# corex2.net
KiCad netlist of a schematic drawn in EAGLE
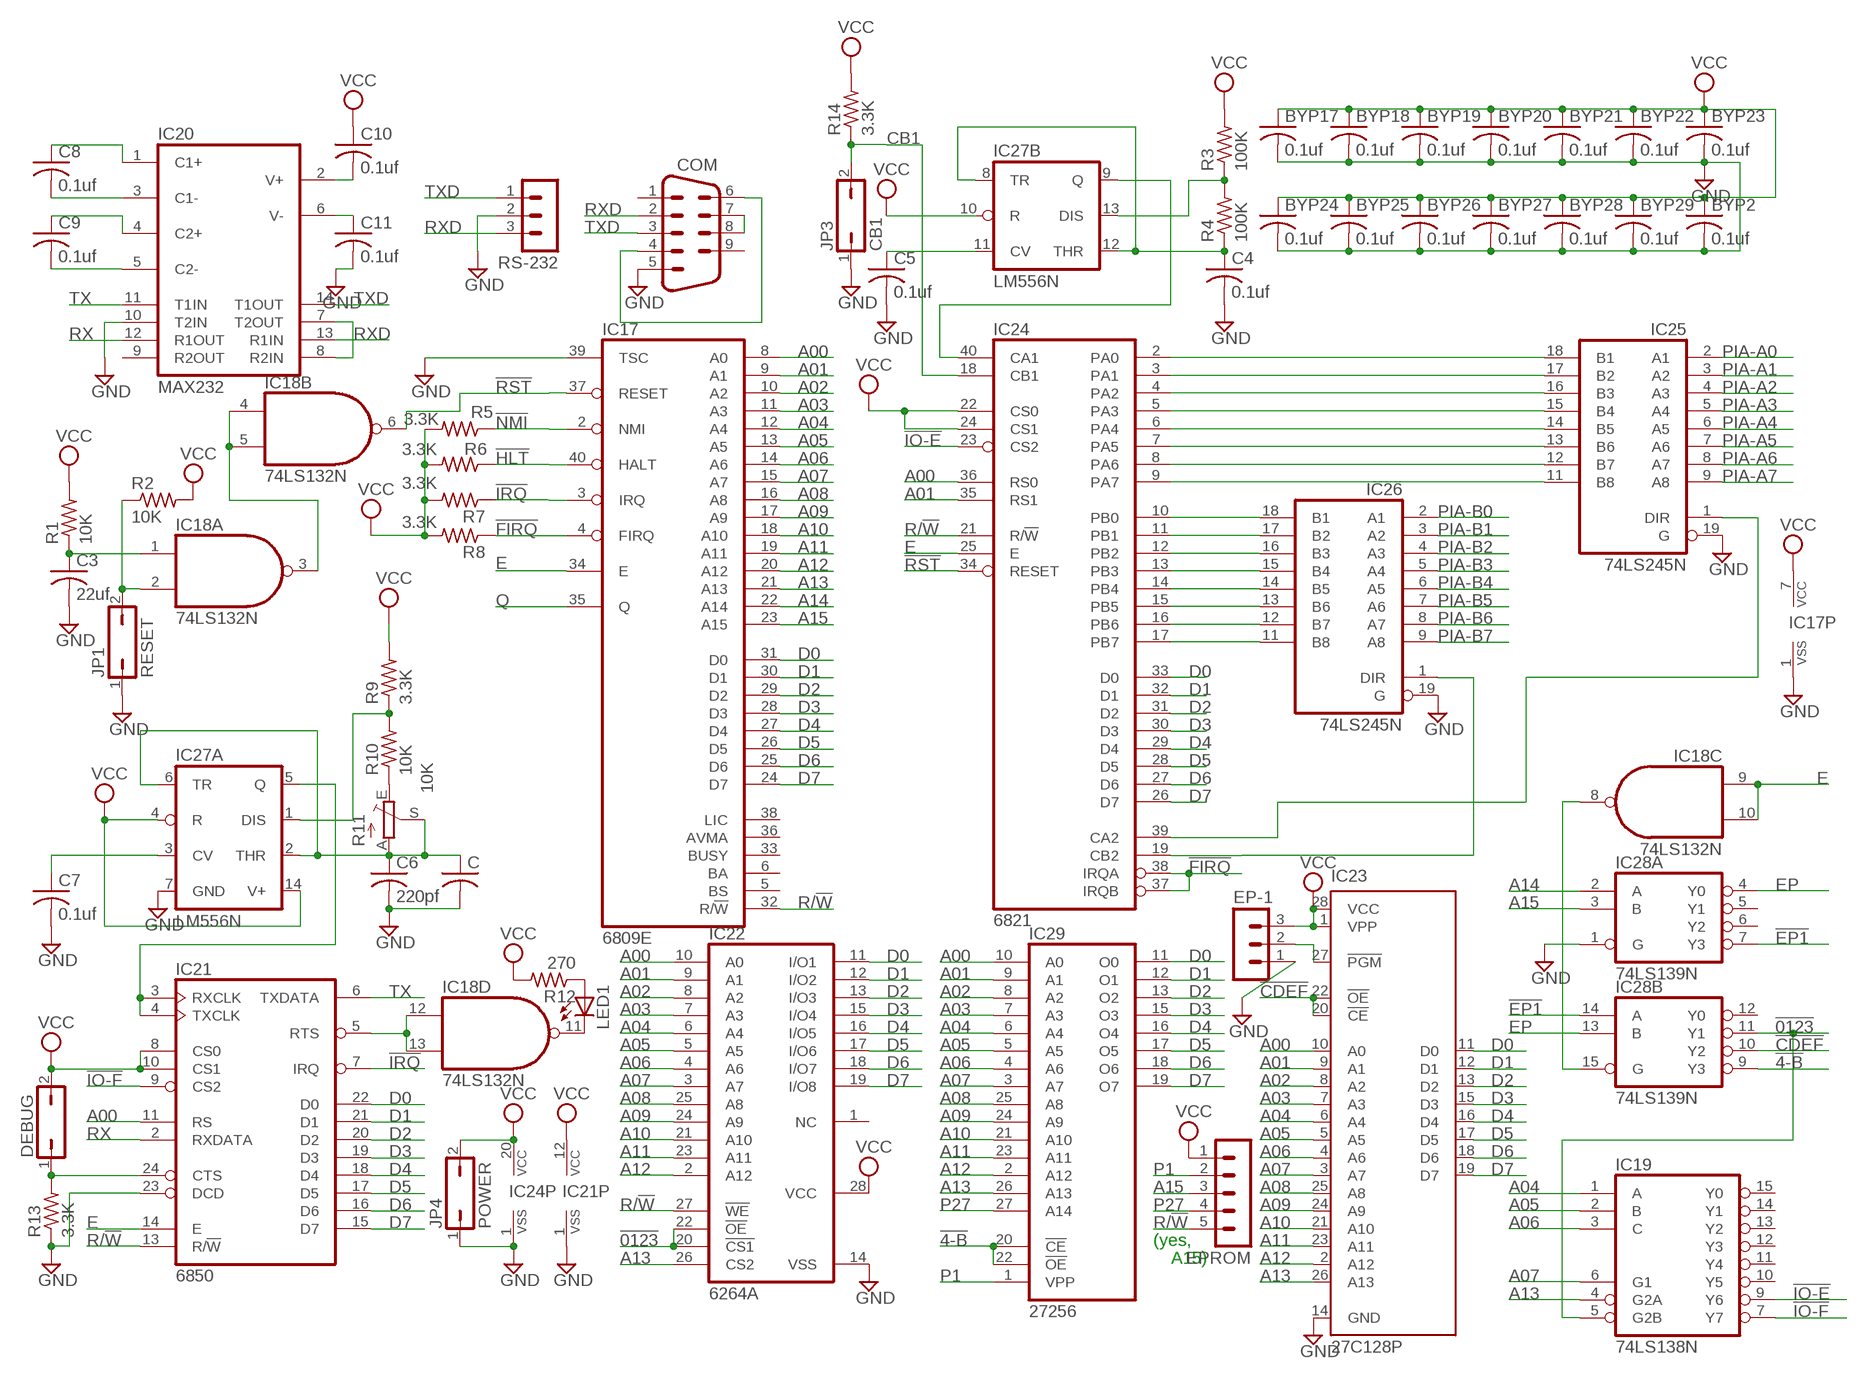
[diagram p0: schematic, sheet 1]
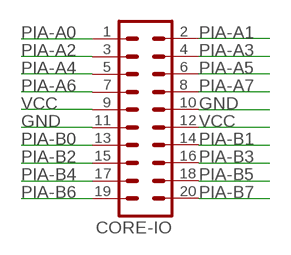
[diagram p1: schematic, sheet 2]
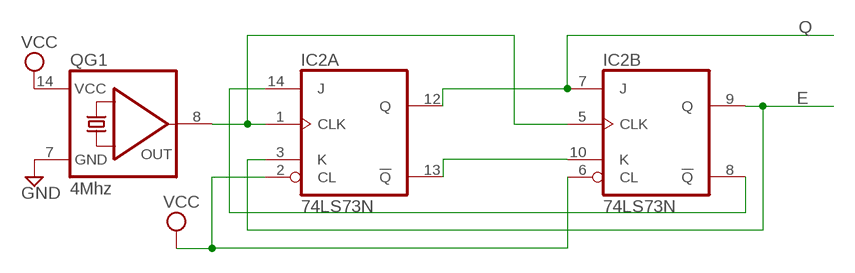
[diagram p2: schematic, sheet 3]

(export (version "E")
  (design (tool "Eeschema 10.0.6"))
  (components
    (comp (ref "CORE-IO")
      (value "MA10-2")
      (footprint "eagle-import:MA10-2")
      (libsource (lib "eagle-import") (part "MA10-2"))
    )
    (comp (ref "BYP2")
      (value "0.1uf")
      (footprint "eagle-import:C050-025X075")
      (libsource (lib "eagle-import") (part "C-US050-025X075"))
    )
    (comp (ref "BYP17")
      (value "0.1uf")
      (footprint "eagle-import:C050-025X075")
      (libsource (lib "eagle-import") (part "C-US050-025X075"))
    )
    (comp (ref "BYP18")
      (value "0.1uf")
      (footprint "eagle-import:C050-025X075")
      (libsource (lib "eagle-import") (part "C-US050-025X075"))
    )
    (comp (ref "BYP19")
      (value "0.1uf")
      (footprint "eagle-import:C050-025X075")
      (libsource (lib "eagle-import") (part "C-US050-025X075"))
    )
    (comp (ref "BYP20")
      (value "0.1uf")
      (footprint "eagle-import:C050-025X075")
      (libsource (lib "eagle-import") (part "C-US050-025X075"))
    )
    (comp (ref "BYP21")
      (value "0.1uf")
      (footprint "eagle-import:C050-025X075")
      (libsource (lib "eagle-import") (part "C-US050-025X075"))
    )
    (comp (ref "BYP22")
      (value "0.1uf")
      (footprint "eagle-import:C050-025X075")
      (libsource (lib "eagle-import") (part "C-US050-025X075"))
    )
    (comp (ref "BYP23")
      (value "0.1uf")
      (footprint "eagle-import:C050-025X075")
      (libsource (lib "eagle-import") (part "C-US050-025X075"))
    )
    (comp (ref "BYP24")
      (value "0.1uf")
      (footprint "eagle-import:C050-025X075")
      (libsource (lib "eagle-import") (part "C-US050-025X075"))
    )
    (comp (ref "BYP25")
      (value "0.1uf")
      (footprint "eagle-import:C050-025X075")
      (libsource (lib "eagle-import") (part "C-US050-025X075"))
    )
    (comp (ref "BYP26")
      (value "0.1uf")
      (footprint "eagle-import:C050-025X075")
      (libsource (lib "eagle-import") (part "C-US050-025X075"))
    )
    (comp (ref "BYP27")
      (value "0.1uf")
      (footprint "eagle-import:C050-025X075")
      (libsource (lib "eagle-import") (part "C-US050-025X075"))
    )
    (comp (ref "BYP28")
      (value "0.1uf")
      (footprint "eagle-import:C050-025X075")
      (libsource (lib "eagle-import") (part "C-US050-025X075"))
    )
    (comp (ref "BYP29")
      (value "0.1uf")
      (footprint "eagle-import:C050-025X075")
      (libsource (lib "eagle-import") (part "C-US050-025X075"))
    )
    (comp (ref "C")
      (value "C-US050-025X075")
      (footprint "eagle-import:C050-025X075")
      (libsource (lib "eagle-import") (part "C-US050-025X075"))
    )
    (comp (ref "C3")
      (value "22uf")
      (footprint "eagle-import:C102-054X133")
      (libsource (lib "eagle-import") (part "C-US102-054X133"))
    )
    (comp (ref "C4")
      (value "0.1uf")
      (footprint "eagle-import:C050-025X075")
      (libsource (lib "eagle-import") (part "C-US050-025X075"))
    )
    (comp (ref "C5")
      (value "0.1uf")
      (footprint "eagle-import:C050-025X075")
      (libsource (lib "eagle-import") (part "C-US050-025X075"))
    )
    (comp (ref "C6")
      (value "220pf")
      (footprint "eagle-import:C050-025X075")
      (libsource (lib "eagle-import") (part "C-US050-025X075"))
    )
    (comp (ref "C7")
      (value "0.1uf")
      (footprint "eagle-import:C050-025X075")
      (libsource (lib "eagle-import") (part "C-US050-025X075"))
    )
    (comp (ref "C8")
      (value "0.1uf")
      (footprint "eagle-import:C050-025X075")
      (libsource (lib "eagle-import") (part "C-US050-025X075"))
    )
    (comp (ref "C9")
      (value "0.1uf")
      (footprint "eagle-import:C050-025X075")
      (libsource (lib "eagle-import") (part "C-US050-025X075"))
    )
    (comp (ref "C10")
      (value "0.1uf")
      (footprint "eagle-import:C050-025X075")
      (libsource (lib "eagle-import") (part "C-US050-025X075"))
    )
    (comp (ref "C11")
      (value "0.1uf")
      (footprint "eagle-import:C050-025X075")
      (libsource (lib "eagle-import") (part "C-US050-025X075"))
    )
    (comp (ref "COM")
      (value "M09HP")
      (footprint "eagle-import:M09HP")
      (libsource (lib "eagle-import") (part "M09HP"))
    )
    (comp (ref "DEBUG")
      (value "JP1Q")
      (footprint "eagle-import:JP1")
      (libsource (lib "eagle-import") (part "JP1Q"))
    )
    (comp (ref "EP-1")
      (value "MA03-1")
      (footprint "eagle-import:MA03-1")
      (libsource (lib "eagle-import") (part "MA03-1"))
    )
    (comp (ref "EPROM")
      (value "MA05-1")
      (footprint "eagle-import:MA05-1")
      (libsource (lib "eagle-import") (part "MA05-1"))
    )
    (comp (ref "IC17")
      (value "6809E")
      (footprint "eagle-import:DIL40")
      (fields (field (name "MF") "NTE ELECTRONICS") (field (name "MPN") "NTE6809E"))
      (libsource (lib "eagle-import") (part "6809E"))
    )
    (comp (ref "IC18")
      (value "74LS132N")
      (footprint "eagle-import:DIL14")
      (libsource (lib "eagle-import") (part "7400NLS"))
    )
    (comp (ref "IC19")
      (value "74LS138N")
      (footprint "eagle-import:DIL16")
      (libsource (lib "eagle-import") (part "74138NLS"))
    )
    (comp (ref "IC20")
      (value "MAX232")
      (footprint "eagle-import:DIL16")
      (fields (field (name "MF") "MAXIM") (field (name "MPN") "MAX232ACPE+"))
      (libsource (lib "eagle-import") (part "MAX232"))
    )
    (comp (ref "IC21")
      (value "6850")
      (footprint "eagle-import:DIL24")
      (fields (field (name "MF") "NTE ELECTRONICS") (field (name "MPN") "NTE6850"))
      (libsource (lib "eagle-import") (part "6850"))
    )
    (comp (ref "IC22")
      (value "6264A")
      (footprint "eagle-import:DIL28-6")
      (libsource (lib "eagle-import") (part "6264A"))
    )
    (comp (ref "IC23")
      (value "27C128P")
      (footprint "eagle-import:DIL28-6")
      (libsource (lib "eagle-import") (part "27128PC"))
    )
    (comp (ref "IC24")
      (value "6821")
      (footprint "eagle-import:DIL40")
      (fields (field (name "MF") "NTE ELECTRONICS") (field (name "MPN") "NTE6821"))
      (libsource (lib "eagle-import") (part "6821"))
    )
    (comp (ref "IC25")
      (value "74LS245N")
      (footprint "eagle-import:DIL20")
      (libsource (lib "eagle-import") (part "74245NLS"))
    )
    (comp (ref "IC26")
      (value "74LS245N")
      (footprint "eagle-import:DIL20")
      (libsource (lib "eagle-import") (part "74245NLS"))
    )
    (comp (ref "IC27")
      (value "LM556N")
      (footprint "eagle-import:DIL14")
      (libsource (lib "eagle-import") (part "556NLM"))
    )
    (comp (ref "IC28")
      (value "74LS139N")
      (footprint "eagle-import:DIL16")
      (libsource (lib "eagle-import") (part "74139NLS"))
    )
    (comp (ref "IC29")
      (value "27256")
      (footprint "eagle-import:DIL28")
      (libsource (lib "eagle-import") (part "27256"))
    )
    (comp (ref "JP1")
      (value "RESET")
      (footprint "eagle-import:JP1")
      (libsource (lib "eagle-import") (part "JP1Q"))
    )
    (comp (ref "JP3")
      (value "CB1")
      (footprint "eagle-import:JP1")
      (libsource (lib "eagle-import") (part "JP1Q"))
    )
    (comp (ref "JP4")
      (value "POWER")
      (footprint "eagle-import:JP1")
      (libsource (lib "eagle-import") (part "JP1Q"))
    )
    (comp (ref "LED1")
      (value "LED3MM")
      (footprint "eagle-import:LED3MM")
      (libsource (lib "eagle-import") (part "LED3MM"))
    )
    (comp (ref "R1")
      (value "10K")
      (footprint "eagle-import:0207_7")
      (libsource (lib "eagle-import") (part "R-US_0207/7"))
    )
    (comp (ref "R2")
      (value "10K")
      (footprint "eagle-import:0207_7")
      (libsource (lib "eagle-import") (part "R-US_0207/7"))
    )
    (comp (ref "R3")
      (value "100K")
      (footprint "eagle-import:0207_7")
      (libsource (lib "eagle-import") (part "R-US_0207/7"))
    )
    (comp (ref "R4")
      (value "100K")
      (footprint "eagle-import:0207_7")
      (libsource (lib "eagle-import") (part "R-US_0207/7"))
    )
    (comp (ref "R5")
      (value "3.3K")
      (footprint "eagle-import:0207_7")
      (libsource (lib "eagle-import") (part "R-US_0207/7"))
    )
    (comp (ref "R6")
      (value "3.3K")
      (footprint "eagle-import:0207_7")
      (libsource (lib "eagle-import") (part "R-US_0207/7"))
    )
    (comp (ref "R7")
      (value "3.3K")
      (footprint "eagle-import:0207_7")
      (libsource (lib "eagle-import") (part "R-US_0207/7"))
    )
    (comp (ref "R8")
      (value "3.3K")
      (footprint "eagle-import:0207_7")
      (libsource (lib "eagle-import") (part "R-US_0207/7"))
    )
    (comp (ref "R9")
      (value "3.3K")
      (footprint "eagle-import:0207_7")
      (libsource (lib "eagle-import") (part "R-US_0207/7"))
    )
    (comp (ref "R10")
      (value "10K")
      (footprint "eagle-import:0207_7")
      (libsource (lib "eagle-import") (part "R-US_0207/7"))
    )
    (comp (ref "R11")
      (value "10K")
      (footprint "eagle-import:SP19L")
      (libsource (lib "eagle-import") (part "TRIM_EU-B90P"))
    )
    (comp (ref "R12")
      (value "270")
      (footprint "eagle-import:0207_7")
      (libsource (lib "eagle-import") (part "R-US_0207/7"))
    )
    (comp (ref "R13")
      (value "3.3K")
      (footprint "eagle-import:0207_7")
      (libsource (lib "eagle-import") (part "R-US_0207/7"))
    )
    (comp (ref "R14")
      (value "3.3K")
      (footprint "eagle-import:0207_7")
      (libsource (lib "eagle-import") (part "R-US_0207/7"))
    )
    (comp (ref "RS-232")
      (value "MA03-1")
      (footprint "eagle-import:MA03-1")
      (libsource (lib "eagle-import") (part "MA03-1"))
    )
    (comp (ref "IC2")
      (value "74LS73N")
      (footprint "eagle-import:DIL14")
      (libsource (lib "eagle-import") (part "7473NLS"))
    )
    (comp (ref "QG1")
      (value "4Mhz")
      (footprint "eagle-import:DIL14S")
      (libsource (lib "eagle-import") (part "QG5860"))
    )
  )
  (nets
    (net (code "1") (name "A00") (class "Default")
      (node (ref "IC17") (pin "8") (pinfunction "A0_8") (pintype "tri_state"))
      (node (ref "IC21") (pin "11") (pinfunction "RS_11") (pintype "input"))
      (node (ref "IC22") (pin "10") (pinfunction "A0_10") (pintype "input"))
      (node (ref "IC23") (pin "10") (pinfunction "A0_10") (pintype "input"))
      (node (ref "IC24") (pin "36") (pinfunction "RS0_36") (pintype "input"))
      (node (ref "IC29") (pin "10") (pinfunction "A0_10") (pintype "input"))
    )
    (net (code "2") (name "A01") (class "Default")
      (node (ref "IC17") (pin "9") (pinfunction "A1_9") (pintype "tri_state"))
      (node (ref "IC22") (pin "9") (pinfunction "A1_9") (pintype "input"))
      (node (ref "IC23") (pin "9") (pinfunction "A1_9") (pintype "input"))
      (node (ref "IC24") (pin "35") (pinfunction "RS1_35") (pintype "input"))
      (node (ref "IC29") (pin "9") (pinfunction "A1_9") (pintype "input"))
    )
    (net (code "3") (name "A02") (class "Default")
      (node (ref "IC17") (pin "10") (pinfunction "A2_10") (pintype "tri_state"))
      (node (ref "IC22") (pin "8") (pinfunction "A2_8") (pintype "input"))
      (node (ref "IC23") (pin "8") (pinfunction "A2_8") (pintype "input"))
      (node (ref "IC29") (pin "8") (pinfunction "A2_8") (pintype "input"))
    )
    (net (code "4") (name "A03") (class "Default")
      (node (ref "IC17") (pin "11") (pinfunction "A3_11") (pintype "tri_state"))
      (node (ref "IC22") (pin "7") (pinfunction "A3_7") (pintype "input"))
      (node (ref "IC23") (pin "7") (pinfunction "A3_7") (pintype "input"))
      (node (ref "IC29") (pin "7") (pinfunction "A3_7") (pintype "input"))
    )
    (net (code "5") (name "A04") (class "Default")
      (node (ref "IC17") (pin "12") (pinfunction "A4_12") (pintype "tri_state"))
      (node (ref "IC19") (pin "1") (pinfunction "A_1") (pintype "input"))
      (node (ref "IC22") (pin "6") (pinfunction "A4_6") (pintype "input"))
      (node (ref "IC23") (pin "6") (pinfunction "A4_6") (pintype "input"))
      (node (ref "IC29") (pin "6") (pinfunction "A4_6") (pintype "input"))
    )
    (net (code "6") (name "A05") (class "Default")
      (node (ref "IC17") (pin "13") (pinfunction "A5_13") (pintype "tri_state"))
      (node (ref "IC19") (pin "2") (pinfunction "B_2") (pintype "input"))
      (node (ref "IC22") (pin "5") (pinfunction "A5_5") (pintype "input"))
      (node (ref "IC23") (pin "5") (pinfunction "A5_5") (pintype "input"))
      (node (ref "IC29") (pin "5") (pinfunction "A5_5") (pintype "input"))
    )
    (net (code "7") (name "A06") (class "Default")
      (node (ref "IC17") (pin "14") (pinfunction "A6_14") (pintype "tri_state"))
      (node (ref "IC19") (pin "3") (pinfunction "C_3") (pintype "input"))
      (node (ref "IC22") (pin "4") (pinfunction "A6_4") (pintype "input"))
      (node (ref "IC23") (pin "4") (pinfunction "A6_4") (pintype "input"))
      (node (ref "IC29") (pin "4") (pinfunction "A6_4") (pintype "input"))
    )
    (net (code "8") (name "A07") (class "Default")
      (node (ref "IC17") (pin "15") (pinfunction "A7_15") (pintype "tri_state"))
      (node (ref "IC19") (pin "6") (pinfunction "G1_6") (pintype "input"))
      (node (ref "IC22") (pin "3") (pinfunction "A7_3") (pintype "input"))
      (node (ref "IC23") (pin "3") (pinfunction "A7_3") (pintype "input"))
      (node (ref "IC29") (pin "3") (pinfunction "A7_3") (pintype "input"))
    )
    (net (code "9") (name "A08") (class "Default")
      (node (ref "IC17") (pin "16") (pinfunction "A8_16") (pintype "tri_state"))
      (node (ref "IC22") (pin "25") (pinfunction "A8_25") (pintype "input"))
      (node (ref "IC23") (pin "25") (pinfunction "A8_25") (pintype "input"))
      (node (ref "IC29") (pin "25") (pinfunction "A8_25") (pintype "input"))
    )
    (net (code "10") (name "A09") (class "Default")
      (node (ref "IC17") (pin "17") (pinfunction "A9_17") (pintype "tri_state"))
      (node (ref "IC22") (pin "24") (pinfunction "A9_24") (pintype "input"))
      (node (ref "IC23") (pin "24") (pinfunction "A9_24") (pintype "input"))
      (node (ref "IC29") (pin "24") (pinfunction "A9_24") (pintype "input"))
    )
    (net (code "11") (name "A10") (class "Default")
      (node (ref "IC17") (pin "18") (pinfunction "A10_18") (pintype "tri_state"))
      (node (ref "IC22") (pin "21") (pinfunction "A10_21") (pintype "input"))
      (node (ref "IC23") (pin "21") (pinfunction "A10_21") (pintype "input"))
      (node (ref "IC29") (pin "21") (pinfunction "A10_21") (pintype "input"))
    )
    (net (code "12") (name "A11") (class "Default")
      (node (ref "IC17") (pin "19") (pinfunction "A11_19") (pintype "tri_state"))
      (node (ref "IC22") (pin "23") (pinfunction "A11_23") (pintype "input"))
      (node (ref "IC23") (pin "23") (pinfunction "A11_23") (pintype "input"))
      (node (ref "IC29") (pin "23") (pinfunction "A11_23") (pintype "input"))
    )
    (net (code "13") (name "A12") (class "Default")
      (node (ref "IC17") (pin "20") (pinfunction "A12_20") (pintype "tri_state"))
      (node (ref "IC22") (pin "2") (pinfunction "A12_2") (pintype "input"))
      (node (ref "IC23") (pin "2") (pinfunction "A12_2") (pintype "input"))
      (node (ref "IC29") (pin "2") (pinfunction "A12_2") (pintype "input"))
    )
    (net (code "14") (name "A13") (class "Default")
      (node (ref "IC17") (pin "21") (pinfunction "A13_21") (pintype "tri_state"))
      (node (ref "IC19") (pin "4") (pinfunction "G2A_4") (pintype "input"))
      (node (ref "IC22") (pin "26") (pinfunction "CS2_26") (pintype "input"))
      (node (ref "IC23") (pin "26") (pinfunction "A13_26") (pintype "input"))
      (node (ref "IC29") (pin "26") (pinfunction "A13_26") (pintype "input"))
    )
    (net (code "15") (name "A14") (class "Default")
      (node (ref "IC17") (pin "22") (pinfunction "A14_22") (pintype "tri_state"))
      (node (ref "IC28") (pin "2") (pinfunction "A_2") (pintype "input"))
    )
    (net (code "16") (name "A15") (class "Default")
      (node (ref "EPROM") (pin "3") (pinfunction "3_3") (pintype "passive"))
      (node (ref "IC17") (pin "23") (pinfunction "A15_23") (pintype "tri_state"))
      (node (ref "IC28") (pin "3") (pinfunction "B_3") (pintype "input"))
    )
    (net (code "17") (name "CB1") (class "Default")
      (node (ref "IC24") (pin "18") (pinfunction "CB1_18") (pintype "input"))
      (node (ref "JP3") (pin "2") (pinfunction "2_2") (pintype "passive"))
      (node (ref "R14") (pin "1") (pinfunction "1_1") (pintype "passive"))
    )
    (net (code "18") (name "D0") (class "Default")
      (node (ref "IC17") (pin "31") (pinfunction "D0_31") (pintype "bidirectional"))
      (node (ref "IC21") (pin "22") (pinfunction "D0_22") (pintype "bidirectional"))
      (node (ref "IC22") (pin "11") (pinfunction "I/O1_11") (pintype "bidirectional"))
      (node (ref "IC23") (pin "11") (pinfunction "D0_11") (pintype "tri_state"))
      (node (ref "IC24") (pin "33") (pinfunction "D0_33") (pintype "bidirectional"))
      (node (ref "IC29") (pin "11") (pinfunction "O0_11") (pintype "tri_state"))
    )
    (net (code "19") (name "D1") (class "Default")
      (node (ref "IC17") (pin "30") (pinfunction "D1_30") (pintype "bidirectional"))
      (node (ref "IC21") (pin "21") (pinfunction "D1_21") (pintype "bidirectional"))
      (node (ref "IC22") (pin "12") (pinfunction "I/O2_12") (pintype "bidirectional"))
      (node (ref "IC23") (pin "12") (pinfunction "D1_12") (pintype "tri_state"))
      (node (ref "IC24") (pin "32") (pinfunction "D1_32") (pintype "bidirectional"))
      (node (ref "IC29") (pin "12") (pinfunction "O1_12") (pintype "tri_state"))
    )
    (net (code "20") (name "D2") (class "Default")
      (node (ref "IC17") (pin "29") (pinfunction "D2_29") (pintype "bidirectional"))
      (node (ref "IC21") (pin "20") (pinfunction "D2_20") (pintype "bidirectional"))
      (node (ref "IC22") (pin "13") (pinfunction "I/O3_13") (pintype "bidirectional"))
      (node (ref "IC23") (pin "13") (pinfunction "D2_13") (pintype "tri_state"))
      (node (ref "IC24") (pin "31") (pinfunction "D2_31") (pintype "bidirectional"))
      (node (ref "IC29") (pin "13") (pinfunction "O2_13") (pintype "tri_state"))
    )
    (net (code "21") (name "D3") (class "Default")
      (node (ref "IC17") (pin "28") (pinfunction "D3_28") (pintype "bidirectional"))
      (node (ref "IC21") (pin "19") (pinfunction "D3_19") (pintype "bidirectional"))
      (node (ref "IC22") (pin "15") (pinfunction "I/O4_15") (pintype "bidirectional"))
      (node (ref "IC23") (pin "15") (pinfunction "D3_15") (pintype "tri_state"))
      (node (ref "IC24") (pin "30") (pinfunction "D3_30") (pintype "bidirectional"))
      (node (ref "IC29") (pin "15") (pinfunction "O3_15") (pintype "tri_state"))
    )
    (net (code "22") (name "D4") (class "Default")
      (node (ref "IC17") (pin "27") (pinfunction "D4_27") (pintype "bidirectional"))
      (node (ref "IC21") (pin "18") (pinfunction "D4_18") (pintype "bidirectional"))
      (node (ref "IC22") (pin "16") (pinfunction "I/O5_16") (pintype "bidirectional"))
      (node (ref "IC23") (pin "16") (pinfunction "D4_16") (pintype "tri_state"))
      (node (ref "IC24") (pin "29") (pinfunction "D4_29") (pintype "bidirectional"))
      (node (ref "IC29") (pin "16") (pinfunction "O4_16") (pintype "tri_state"))
    )
    (net (code "23") (name "D5") (class "Default")
      (node (ref "IC17") (pin "26") (pinfunction "D5_26") (pintype "bidirectional"))
      (node (ref "IC21") (pin "17") (pinfunction "D5_17") (pintype "bidirectional"))
      (node (ref "IC22") (pin "17") (pinfunction "I/O6_17") (pintype "bidirectional"))
      (node (ref "IC23") (pin "17") (pinfunction "D5_17") (pintype "tri_state"))
      (node (ref "IC24") (pin "28") (pinfunction "D5_28") (pintype "bidirectional"))
      (node (ref "IC29") (pin "17") (pinfunction "O5_17") (pintype "tri_state"))
    )
    (net (code "24") (name "D6") (class "Default")
      (node (ref "IC17") (pin "25") (pinfunction "D6_25") (pintype "bidirectional"))
      (node (ref "IC21") (pin "16") (pinfunction "D6_16") (pintype "bidirectional"))
      (node (ref "IC22") (pin "18") (pinfunction "I/O7_18") (pintype "bidirectional"))
      (node (ref "IC23") (pin "18") (pinfunction "D6_18") (pintype "tri_state"))
      (node (ref "IC24") (pin "27") (pinfunction "D6_27") (pintype "bidirectional"))
      (node (ref "IC29") (pin "18") (pinfunction "O6_18") (pintype "tri_state"))
    )
    (net (code "25") (name "D7") (class "Default")
      (node (ref "IC17") (pin "24") (pinfunction "D7_24") (pintype "bidirectional"))
      (node (ref "IC21") (pin "15") (pinfunction "D7_15") (pintype "bidirectional"))
      (node (ref "IC22") (pin "19") (pinfunction "I/O8_19") (pintype "bidirectional"))
      (node (ref "IC23") (pin "19") (pinfunction "D7_19") (pintype "tri_state"))
      (node (ref "IC24") (pin "26") (pinfunction "D7_26") (pintype "bidirectional"))
      (node (ref "IC29") (pin "19") (pinfunction "O7_19") (pintype "tri_state"))
    )
    (net (code "26") (name "E") (class "Default")
      (node (ref "IC17") (pin "34") (pinfunction "E_34") (pintype "input"))
      (node (ref "IC18") (pin "10") (pinfunction "I1_10") (pintype "input"))
      (node (ref "IC18") (pin "9") (pinfunction "I0_9") (pintype "input"))
      (node (ref "IC2") (pin "3") (pinfunction "K_3") (pintype "input"))
      (node (ref "IC2") (pin "9") (pinfunction "Q_9") (pintype "output"))
      (node (ref "IC21") (pin "14") (pinfunction "E_14") (pintype "input"))
      (node (ref "IC24") (pin "25") (pinfunction "E_25") (pintype "input"))
    )
    (net (code "27") (name "EP") (class "Default")
      (node (ref "IC28") (pin "13") (pinfunction "B_13") (pintype "input"))
      (node (ref "IC28") (pin "4") (pinfunction "Y0_4") (pintype "output"))
    )
    (net (code "28") (name "GND") (class "Default")
      (node (ref "BYP17") (pin "2") (pinfunction "2_2") (pintype "passive"))
      (node (ref "BYP18") (pin "2") (pinfunction "2_2") (pintype "passive"))
      (node (ref "BYP19") (pin "2") (pinfunction "2_2") (pintype "passive"))
      (node (ref "BYP2") (pin "2") (pinfunction "2_2") (pintype "passive"))
      (node (ref "BYP20") (pin "2") (pinfunction "2_2") (pintype "passive"))
      (node (ref "BYP21") (pin "2") (pinfunction "2_2") (pintype "passive"))
      (node (ref "BYP22") (pin "2") (pinfunction "2_2") (pintype "passive"))
      (node (ref "BYP23") (pin "2") (pinfunction "2_2") (pintype "passive"))
      (node (ref "BYP24") (pin "2") (pinfunction "2_2") (pintype "passive"))
      (node (ref "BYP25") (pin "2") (pinfunction "2_2") (pintype "passive"))
      (node (ref "BYP26") (pin "2") (pinfunction "2_2") (pintype "passive"))
      (node (ref "BYP27") (pin "2") (pinfunction "2_2") (pintype "passive"))
      (node (ref "BYP28") (pin "2") (pinfunction "2_2") (pintype "passive"))
      (node (ref "BYP29") (pin "2") (pinfunction "2_2") (pintype "passive"))
      (node (ref "C") (pin "2") (pinfunction "2_2") (pintype "passive"))
      (node (ref "C11") (pin "2") (pinfunction "2_2") (pintype "passive"))
      (node (ref "C3") (pin "2") (pinfunction "2_2") (pintype "passive"))
      (node (ref "C4") (pin "2") (pinfunction "2_2") (pintype "passive"))
      (node (ref "C5") (pin "2") (pinfunction "2_2") (pintype "passive"))
      (node (ref "C6") (pin "2") (pinfunction "2_2") (pintype "passive"))
      (node (ref "C7") (pin "2") (pinfunction "2_2") (pintype "passive"))
      (node (ref "COM") (pin "5") (pinfunction "5_5") (pintype "passive"))
      (node (ref "CORE-IO") (pin "10") (pinfunction "10_10") (pintype "passive"))
      (node (ref "CORE-IO") (pin "11") (pinfunction "11_11") (pintype "passive"))
      (node (ref "EP-1") (pin "1") (pinfunction "1_1") (pintype "passive"))
      (node (ref "IC17") (pin "1") (pinfunction "VSS_1") (pintype "power_in"))
      (node (ref "IC17") (pin "39") (pinfunction "TSC_39") (pintype "input"))
      (node (ref "IC20") (pin "10") (pinfunction "T2IN_10") (pintype "input"))
      (node (ref "IC21") (pin "1") (pinfunction "VSS_1") (pintype "power_in"))
      (node (ref "IC21") (pin "23") (pinfunction "DCD_23") (pintype "input"))
      (node (ref "IC22") (pin "14") (pinfunction "VSS_14") (pintype "power_in"))
      (node (ref "IC23") (pin "14") (pinfunction "GND_14") (pintype "power_in"))
      (node (ref "IC24") (pin "1") (pinfunction "VSS_1") (pintype "power_in"))
      (node (ref "IC25") (pin "19") (pinfunction "G_19") (pintype "input"))
      (node (ref "IC26") (pin "19") (pinfunction "G_19") (pintype "input"))
      (node (ref "IC27") (pin "7") (pinfunction "GND_7") (pintype "power_in"))
      (node (ref "IC28") (pin "1") (pinfunction "G_1") (pintype "input"))
      (node (ref "JP1") (pin "1") (pinfunction "1_1") (pintype "passive"))
      (node (ref "JP3") (pin "1") (pinfunction "1_1") (pintype "passive"))
      (node (ref "JP4") (pin "1") (pinfunction "1_1") (pintype "passive"))
      (node (ref "QG1") (pin "7") (pinfunction "GND_7") (pintype "power_in"))
      (node (ref "R13") (pin "1") (pinfunction "1_1") (pintype "passive"))
      (node (ref "RS-232") (pin "2") (pinfunction "2_2") (pintype "passive"))
    )
    (net (code "29") (name "Net-(COM-Pad4)") (class "Default")
      (node (ref "COM") (pin "4") (pinfunction "4_4") (pintype "passive"))
      (node (ref "COM") (pin "6") (pinfunction "6_6") (pintype "passive"))
    )
    (net (code "30") (name "Net-(COM-Pad7)") (class "Default")
      (node (ref "COM") (pin "7") (pinfunction "7_7") (pintype "passive"))
      (node (ref "COM") (pin "8") (pinfunction "8_8") (pintype "passive"))
    )
    (net (code "31") (name "Net-(IC2A-CLK)") (class "Default")
      (node (ref "IC2") (pin "1") (pinfunction "CLK_1") (pintype "input"))
      (node (ref "IC2") (pin "5") (pinfunction "CLK_5") (pintype "input"))
      (node (ref "QG1") (pin "8") (pinfunction "OUT_8") (pintype "output"))
    )
    (net (code "32") (name "Net-(IC2A-J)") (class "Default")
      (node (ref "IC2") (pin "14") (pinfunction "J_14") (pintype "input"))
      (node (ref "IC2") (pin "8") (pinfunction "~{Q}_8") (pintype "output"))
    )
    (net (code "33") (name "Net-(IC2A-~{Q})") (class "Default")
      (node (ref "IC2") (pin "10") (pinfunction "K_10") (pintype "input"))
      (node (ref "IC2") (pin "13") (pinfunction "~{Q}_13") (pintype "output"))
    )
    (net (code "34") (name "Net-(IC18A-I0)") (class "Default")
      (node (ref "C3") (pin "1") (pinfunction "1_1") (pintype "passive"))
      (node (ref "IC18") (pin "1") (pinfunction "I0_1") (pintype "input"))
      (node (ref "R1") (pin "1") (pinfunction "1_1") (pintype "passive"))
    )
    (net (code "35") (name "Net-(IC18A-I1)") (class "Default")
      (node (ref "IC18") (pin "2") (pinfunction "I1_2") (pintype "input"))
      (node (ref "JP1") (pin "2") (pinfunction "2_2") (pintype "passive"))
      (node (ref "R2") (pin "1") (pinfunction "1_1") (pintype "passive"))
    )
    (net (code "36") (name "Net-(IC18A-O)") (class "Default")
      (node (ref "IC18") (pin "3") (pinfunction "O_3") (pintype "output"))
      (node (ref "IC18") (pin "4") (pinfunction "I0_4") (pintype "input"))
      (node (ref "IC18") (pin "5") (pinfunction "I1_5") (pintype "input"))
    )
    (net (code "37") (name "Net-(IC18C-O)") (class "Default")
      (node (ref "IC18") (pin "8") (pinfunction "O_8") (pintype "output"))
      (node (ref "IC28") (pin "15") (pinfunction "G_15") (pintype "input"))
    )
    (net (code "38") (name "Net-(IC18D-I0)") (class "Default")
      (node (ref "IC18") (pin "12") (pinfunction "I0_12") (pintype "input"))
      (node (ref "IC18") (pin "13") (pinfunction "I1_13") (pintype "input"))
      (node (ref "IC21") (pin "5") (pinfunction "RTS_5") (pintype "output"))
    )
    (net (code "39") (name "Net-(IC18D-O)") (class "Default")
      (node (ref "IC18") (pin "11") (pinfunction "O_11") (pintype "output"))
      (node (ref "LED1") (pin "K") (pinfunction "C_K") (pintype "passive"))
    )
    (net (code "40") (name "Net-(IC20A-C1+)") (class "Default")
      (node (ref "C8") (pin "1") (pinfunction "1_1") (pintype "passive"))
      (node (ref "IC20") (pin "1") (pinfunction "C1+_1") (pintype "bidirectional"))
    )
    (net (code "41") (name "Net-(IC20A-C1-)") (class "Default")
      (node (ref "C8") (pin "2") (pinfunction "2_2") (pintype "passive"))
      (node (ref "IC20") (pin "3") (pinfunction "C1-_3") (pintype "bidirectional"))
    )
    (net (code "42") (name "Net-(IC20A-C2+)") (class "Default")
      (node (ref "C9") (pin "1") (pinfunction "1_1") (pintype "passive"))
      (node (ref "IC20") (pin "4") (pinfunction "C2+_4") (pintype "bidirectional"))
    )
    (net (code "43") (name "Net-(IC20A-C2-)") (class "Default")
      (node (ref "C9") (pin "2") (pinfunction "2_2") (pintype "passive"))
      (node (ref "IC20") (pin "5") (pinfunction "C2-_5") (pintype "bidirectional"))
    )
    (net (code "44") (name "Net-(IC20A-R2IN)") (class "Default")
      (node (ref "IC20") (pin "7") (pinfunction "T2OUT_7") (pintype "output"))
      (node (ref "IC20") (pin "8") (pinfunction "R2IN_8") (pintype "input"))
    )
    (net (code "45") (name "Net-(IC20A-V+)") (class "Default")
      (node (ref "C10") (pin "2") (pinfunction "2_2") (pintype "passive"))
      (node (ref "IC20") (pin "2") (pinfunction "V+_2") (pintype "bidirectional"))
    )
    (net (code "46") (name "Net-(IC20A-V-)") (class "Default")
      (node (ref "C11") (pin "1") (pinfunction "1_1") (pintype "passive"))
      (node (ref "IC20") (pin "6") (pinfunction "V-_6") (pintype "bidirectional"))
    )
    (net (code "47") (name "Net-(IC21A-CTS)") (class "Default")
      (node (ref "DEBUG") (pin "1") (pinfunction "1_1") (pintype "passive"))
      (node (ref "IC21") (pin "24") (pinfunction "CTS_24") (pintype "input"))
      (node (ref "R13") (pin "2") (pinfunction "2_2") (pintype "passive"))
    )
    (net (code "48") (name "Net-(IC21A-RXCLK)") (class "Default")
      (node (ref "IC21") (pin "3") (pinfunction "RXCLK_3") (pintype "input"))
      (node (ref "IC21") (pin "4") (pinfunction "TXCLK_4") (pintype "input"))
      (node (ref "IC27") (pin "5") (pinfunction "Q_5") (pintype "output"))
    )
    (net (code "49") (name "Net-(IC23-~{PGM})") (class "Default")
      (node (ref "EP-1") (pin "2") (pinfunction "2_2") (pintype "passive"))
      (node (ref "IC23") (pin "27") (pinfunction "~{PGM}_27") (pintype "passive"))
    )
    (net (code "50") (name "Net-(IC24A-CA1)") (class "Default")
      (node (ref "IC24") (pin "40") (pinfunction "CA1_40") (pintype "input"))
      (node (ref "IC27") (pin "9") (pinfunction "Q_9") (pintype "output"))
    )
    (net (code "51") (name "Net-(IC24A-CA2)") (class "Default")
      (node (ref "IC24") (pin "39") (pinfunction "CA2_39") (pintype "bidirectional"))
      (node (ref "IC25") (pin "1") (pinfunction "DIR_1") (pintype "input"))
    )
    (net (code "52") (name "Net-(IC24A-CB2)") (class "Default")
      (node (ref "IC24") (pin "19") (pinfunction "CB2_19") (pintype "bidirectional"))
      (node (ref "IC26") (pin "1") (pinfunction "DIR_1") (pintype "input"))
    )
    (net (code "53") (name "Net-(IC24A-PA0)") (class "Default")
      (node (ref "IC24") (pin "2") (pinfunction "PA0_2") (pintype "bidirectional"))
      (node (ref "IC25") (pin "18") (pinfunction "B1_18") (pintype "bidirectional"))
    )
    (net (code "54") (name "Net-(IC24A-PA1)") (class "Default")
      (node (ref "IC24") (pin "3") (pinfunction "PA1_3") (pintype "bidirectional"))
      (node (ref "IC25") (pin "17") (pinfunction "B2_17") (pintype "bidirectional"))
    )
    (net (code "55") (name "Net-(IC24A-PA2)") (class "Default")
      (node (ref "IC24") (pin "4") (pinfunction "PA2_4") (pintype "bidirectional"))
      (node (ref "IC25") (pin "16") (pinfunction "B3_16") (pintype "bidirectional"))
    )
    (net (code "56") (name "Net-(IC24A-PA3)") (class "Default")
      (node (ref "IC24") (pin "5") (pinfunction "PA3_5") (pintype "bidirectional"))
      (node (ref "IC25") (pin "15") (pinfunction "B4_15") (pintype "bidirectional"))
    )
    (net (code "57") (name "Net-(IC24A-PA4)") (class "Default")
      (node (ref "IC24") (pin "6") (pinfunction "PA4_6") (pintype "bidirectional"))
      (node (ref "IC25") (pin "14") (pinfunction "B5_14") (pintype "bidirectional"))
    )
    (net (code "58") (name "Net-(IC24A-PA5)") (class "Default")
      (node (ref "IC24") (pin "7") (pinfunction "PA5_7") (pintype "bidirectional"))
      (node (ref "IC25") (pin "13") (pinfunction "B6_13") (pintype "bidirectional"))
    )
    (net (code "59") (name "Net-(IC24A-PA6)") (class "Default")
      (node (ref "IC24") (pin "8") (pinfunction "PA6_8") (pintype "bidirectional"))
      (node (ref "IC25") (pin "12") (pinfunction "B7_12") (pintype "bidirectional"))
    )
    (net (code "60") (name "Net-(IC24A-PA7)") (class "Default")
      (node (ref "IC24") (pin "9") (pinfunction "PA7_9") (pintype "bidirectional"))
      (node (ref "IC25") (pin "11") (pinfunction "B8_11") (pintype "bidirectional"))
    )
    (net (code "61") (name "Net-(IC24A-PB0)") (class "Default")
      (node (ref "IC24") (pin "10") (pinfunction "PB0_10") (pintype "bidirectional"))
      (node (ref "IC26") (pin "18") (pinfunction "B1_18") (pintype "bidirectional"))
    )
    (net (code "62") (name "Net-(IC24A-PB1)") (class "Default")
      (node (ref "IC24") (pin "11") (pinfunction "PB1_11") (pintype "bidirectional"))
      (node (ref "IC26") (pin "17") (pinfunction "B2_17") (pintype "bidirectional"))
    )
    (net (code "63") (name "Net-(IC24A-PB2)") (class "Default")
      (node (ref "IC24") (pin "12") (pinfunction "PB2_12") (pintype "bidirectional"))
      (node (ref "IC26") (pin "16") (pinfunction "B3_16") (pintype "bidirectional"))
    )
    (net (code "64") (name "Net-(IC24A-PB3)") (class "Default")
      (node (ref "IC24") (pin "13") (pinfunction "PB3_13") (pintype "bidirectional"))
      (node (ref "IC26") (pin "15") (pinfunction "B4_15") (pintype "bidirectional"))
    )
    (net (code "65") (name "Net-(IC24A-PB4)") (class "Default")
      (node (ref "IC24") (pin "14") (pinfunction "PB4_14") (pintype "bidirectional"))
      (node (ref "IC26") (pin "14") (pinfunction "B5_14") (pintype "bidirectional"))
    )
    (net (code "66") (name "Net-(IC24A-PB5)") (class "Default")
      (node (ref "IC24") (pin "15") (pinfunction "PB5_15") (pintype "bidirectional"))
      (node (ref "IC26") (pin "13") (pinfunction "B6_13") (pintype "bidirectional"))
    )
    (net (code "67") (name "Net-(IC24A-PB6)") (class "Default")
      (node (ref "IC24") (pin "16") (pinfunction "PB6_16") (pintype "bidirectional"))
      (node (ref "IC26") (pin "12") (pinfunction "B7_12") (pintype "bidirectional"))
    )
    (net (code "68") (name "Net-(IC24A-PB7)") (class "Default")
      (node (ref "IC24") (pin "17") (pinfunction "PB7_17") (pintype "bidirectional"))
      (node (ref "IC26") (pin "11") (pinfunction "B8_11") (pintype "bidirectional"))
    )
    (net (code "69") (name "Net-(IC27A-CV)") (class "Default")
      (node (ref "C7") (pin "1") (pinfunction "1_1") (pintype "passive"))
      (node (ref "IC27") (pin "3") (pinfunction "CV_3") (pintype "input"))
    )
    (net (code "70") (name "Net-(IC27A-DIS)") (class "Default")
      (node (ref "IC27") (pin "1") (pinfunction "DIS_1") (pintype "input"))
      (node (ref "R10") (pin "2") (pinfunction "2_2") (pintype "passive"))
      (node (ref "R9") (pin "1") (pinfunction "1_1") (pintype "passive"))
    )
    (net (code "71") (name "Net-(IC27A-THR)") (class "Default")
      (node (ref "C") (pin "1") (pinfunction "1_1") (pintype "passive"))
      (node (ref "C6") (pin "1") (pinfunction "1_1") (pintype "passive"))
      (node (ref "IC27") (pin "2") (pinfunction "THR_2") (pintype "input"))
      (node (ref "IC27") (pin "6") (pinfunction "TR_6") (pintype "input"))
      (node (ref "R11") (pin "A") (pinfunction "A_A") (pintype "passive"))
      (node (ref "R11") (pin "S") (pinfunction "S_S") (pintype "passive"))
    )
    (net (code "72") (name "Net-(IC27B-CV)") (class "Default")
      (node (ref "C5") (pin "1") (pinfunction "1_1") (pintype "passive"))
      (node (ref "IC27") (pin "11") (pinfunction "CV_11") (pintype "input"))
    )
    (net (code "73") (name "Net-(IC27B-DIS)") (class "Default")
      (node (ref "IC27") (pin "13") (pinfunction "DIS_13") (pintype "input"))
      (node (ref "R3") (pin "1") (pinfunction "1_1") (pintype "passive"))
      (node (ref "R4") (pin "2") (pinfunction "2_2") (pintype "passive"))
    )
    (net (code "74") (name "Net-(IC27B-THR)") (class "Default")
      (node (ref "C4") (pin "1") (pinfunction "1_1") (pintype "passive"))
      (node (ref "IC27") (pin "12") (pinfunction "THR_12") (pintype "input"))
      (node (ref "IC27") (pin "8") (pinfunction "TR_8") (pintype "input"))
      (node (ref "R4") (pin "1") (pinfunction "1_1") (pintype "passive"))
    )
    (net (code "75") (name "Net-(LED1-PadA)") (class "Default")
      (node (ref "LED1") (pin "A") (pinfunction "A_A") (pintype "passive"))
      (node (ref "R12") (pin "1") (pinfunction "1_1") (pintype "passive"))
    )
    (net (code "76") (name "Net-(R10-Pad1)") (class "Default")
      (node (ref "R10") (pin "1") (pinfunction "1_1") (pintype "passive"))
      (node (ref "R11") (pin "E") (pinfunction "E_E") (pintype "passive"))
    )
    (net (code "77") (name "P1") (class "Default")
      (node (ref "EPROM") (pin "2") (pinfunction "2_2") (pintype "passive"))
      (node (ref "IC29") (pin "1") (pinfunction "VPP_1") (pintype "input"))
    )
    (net (code "78") (name "P27") (class "Default")
      (node (ref "EPROM") (pin "4") (pinfunction "4_4") (pintype "passive"))
      (node (ref "IC29") (pin "27") (pinfunction "A14_27") (pintype "input"))
    )
    (net (code "79") (name "PIA-A0") (class "Default")
      (node (ref "CORE-IO") (pin "1") (pinfunction "1_1") (pintype "passive"))
      (node (ref "IC25") (pin "2") (pinfunction "A1_2") (pintype "bidirectional"))
    )
    (net (code "80") (name "PIA-A1") (class "Default")
      (node (ref "CORE-IO") (pin "2") (pinfunction "2_2") (pintype "passive"))
      (node (ref "IC25") (pin "3") (pinfunction "A2_3") (pintype "bidirectional"))
    )
    (net (code "81") (name "PIA-A2") (class "Default")
      (node (ref "CORE-IO") (pin "3") (pinfunction "3_3") (pintype "passive"))
      (node (ref "IC25") (pin "4") (pinfunction "A3_4") (pintype "bidirectional"))
    )
    (net (code "82") (name "PIA-A3") (class "Default")
      (node (ref "CORE-IO") (pin "4") (pinfunction "4_4") (pintype "passive"))
      (node (ref "IC25") (pin "5") (pinfunction "A4_5") (pintype "bidirectional"))
    )
    (net (code "83") (name "PIA-A4") (class "Default")
      (node (ref "CORE-IO") (pin "5") (pinfunction "5_5") (pintype "passive"))
      (node (ref "IC25") (pin "6") (pinfunction "A5_6") (pintype "bidirectional"))
    )
    (net (code "84") (name "PIA-A5") (class "Default")
      (node (ref "CORE-IO") (pin "6") (pinfunction "6_6") (pintype "passive"))
      (node (ref "IC25") (pin "7") (pinfunction "A6_7") (pintype "bidirectional"))
    )
    (net (code "85") (name "PIA-A6") (class "Default")
      (node (ref "CORE-IO") (pin "7") (pinfunction "7_7") (pintype "passive"))
      (node (ref "IC25") (pin "8") (pinfunction "A7_8") (pintype "bidirectional"))
    )
    (net (code "86") (name "PIA-A7") (class "Default")
      (node (ref "CORE-IO") (pin "8") (pinfunction "8_8") (pintype "passive"))
      (node (ref "IC25") (pin "9") (pinfunction "A8_9") (pintype "bidirectional"))
    )
    (net (code "87") (name "PIA-B0") (class "Default")
      (node (ref "CORE-IO") (pin "13") (pinfunction "13_13") (pintype "passive"))
      (node (ref "IC26") (pin "2") (pinfunction "A1_2") (pintype "bidirectional"))
    )
    (net (code "88") (name "PIA-B1") (class "Default")
      (node (ref "CORE-IO") (pin "14") (pinfunction "14_14") (pintype "passive"))
      (node (ref "IC26") (pin "3") (pinfunction "A2_3") (pintype "bidirectional"))
    )
    (net (code "89") (name "PIA-B2") (class "Default")
      (node (ref "CORE-IO") (pin "15") (pinfunction "15_15") (pintype "passive"))
      (node (ref "IC26") (pin "4") (pinfunction "A3_4") (pintype "bidirectional"))
    )
    (net (code "90") (name "PIA-B3") (class "Default")
      (node (ref "CORE-IO") (pin "16") (pinfunction "16_16") (pintype "passive"))
      (node (ref "IC26") (pin "5") (pinfunction "A4_5") (pintype "bidirectional"))
    )
    (net (code "91") (name "PIA-B4") (class "Default")
      (node (ref "CORE-IO") (pin "17") (pinfunction "17_17") (pintype "passive"))
      (node (ref "IC26") (pin "6") (pinfunction "A5_6") (pintype "bidirectional"))
    )
    (net (code "92") (name "PIA-B5") (class "Default")
      (node (ref "CORE-IO") (pin "18") (pinfunction "18_18") (pintype "passive"))
      (node (ref "IC26") (pin "7") (pinfunction "A6_7") (pintype "bidirectional"))
    )
    (net (code "93") (name "PIA-B6") (class "Default")
      (node (ref "CORE-IO") (pin "19") (pinfunction "19_19") (pintype "passive"))
      (node (ref "IC26") (pin "8") (pinfunction "A7_8") (pintype "bidirectional"))
    )
    (net (code "94") (name "PIA-B7") (class "Default")
      (node (ref "CORE-IO") (pin "20") (pinfunction "20_20") (pintype "passive"))
      (node (ref "IC26") (pin "9") (pinfunction "A8_9") (pintype "bidirectional"))
    )
    (net (code "95") (name "Q") (class "Default")
      (node (ref "IC17") (pin "35") (pinfunction "Q_35") (pintype "input"))
      (node (ref "IC2") (pin "12") (pinfunction "Q_12") (pintype "output"))
      (node (ref "IC2") (pin "7") (pinfunction "J_7") (pintype "input"))
    )
    (net (code "96") (name "RX") (class "Default")
      (node (ref "IC20") (pin "12") (pinfunction "R1OUT_12") (pintype "output"))
      (node (ref "IC21") (pin "2") (pinfunction "RXDATA_2") (pintype "input"))
    )
    (net (code "97") (name "RXD") (class "Default")
      (node (ref "COM") (pin "2") (pinfunction "2_2") (pintype "passive"))
      (node (ref "IC20") (pin "13") (pinfunction "R1IN_13") (pintype "input"))
      (node (ref "RS-232") (pin "3") (pinfunction "3_3") (pintype "passive"))
    )
    (net (code "98") (name "R{slash}~{W}") (class "Default")
      (node (ref "EPROM") (pin "5") (pinfunction "5_5") (pintype "passive"))
      (node (ref "IC17") (pin "32") (pinfunction "R/~{W}_32") (pintype "output"))
      (node (ref "IC21") (pin "13") (pinfunction "R/~{W}_13") (pintype "input"))
      (node (ref "IC22") (pin "27") (pinfunction "~{WE}_27") (pintype "input"))
      (node (ref "IC24") (pin "21") (pinfunction "R/~{W}_21") (pintype "input"))
    )
    (net (code "99") (name "TX") (class "Default")
      (node (ref "IC20") (pin "11") (pinfunction "T1IN_11") (pintype "input"))
      (node (ref "IC21") (pin "6") (pinfunction "TXDATA_6") (pintype "output"))
    )
    (net (code "100") (name "TXD") (class "Default")
      (node (ref "COM") (pin "3") (pinfunction "3_3") (pintype "passive"))
      (node (ref "IC20") (pin "14") (pinfunction "T1OUT_14") (pintype "output"))
      (node (ref "RS-232") (pin "1") (pinfunction "1_1") (pintype "passive"))
    )
    (net (code "101") (name "VCC") (class "Default")
      (node (ref "BYP17") (pin "1") (pinfunction "1_1") (pintype "passive"))
      (node (ref "BYP18") (pin "1") (pinfunction "1_1") (pintype "passive"))
      (node (ref "BYP19") (pin "1") (pinfunction "1_1") (pintype "passive"))
      (node (ref "BYP2") (pin "1") (pinfunction "1_1") (pintype "passive"))
      (node (ref "BYP20") (pin "1") (pinfunction "1_1") (pintype "passive"))
      (node (ref "BYP21") (pin "1") (pinfunction "1_1") (pintype "passive"))
      (node (ref "BYP22") (pin "1") (pinfunction "1_1") (pintype "passive"))
      (node (ref "BYP23") (pin "1") (pinfunction "1_1") (pintype "passive"))
      (node (ref "BYP24") (pin "1") (pinfunction "1_1") (pintype "passive"))
      (node (ref "BYP25") (pin "1") (pinfunction "1_1") (pintype "passive"))
      (node (ref "BYP26") (pin "1") (pinfunction "1_1") (pintype "passive"))
      (node (ref "BYP27") (pin "1") (pinfunction "1_1") (pintype "passive"))
      (node (ref "BYP28") (pin "1") (pinfunction "1_1") (pintype "passive"))
      (node (ref "BYP29") (pin "1") (pinfunction "1_1") (pintype "passive"))
      (node (ref "C10") (pin "1") (pinfunction "1_1") (pintype "passive"))
      (node (ref "CORE-IO") (pin "12") (pinfunction "12_12") (pintype "passive"))
      (node (ref "CORE-IO") (pin "9") (pinfunction "9_9") (pintype "passive"))
      (node (ref "DEBUG") (pin "2") (pinfunction "2_2") (pintype "passive"))
      (node (ref "EP-1") (pin "3") (pinfunction "3_3") (pintype "passive"))
      (node (ref "EPROM") (pin "1") (pinfunction "1_1") (pintype "passive"))
      (node (ref "IC17") (pin "7") (pinfunction "VCC_7") (pintype "power_in"))
      (node (ref "IC2") (pin "2") (pinfunction "CL_2") (pintype "input"))
      (node (ref "IC2") (pin "6") (pinfunction "CL_6") (pintype "input"))
      (node (ref "IC21") (pin "10") (pinfunction "CS1_10") (pintype "input"))
      (node (ref "IC21") (pin "12") (pinfunction "VCC_12") (pintype "power_in"))
      (node (ref "IC21") (pin "8") (pinfunction "CS0_8") (pintype "input"))
      (node (ref "IC22") (pin "28") (pinfunction "VCC_28") (pintype "power_in"))
      (node (ref "IC23") (pin "1") (pinfunction "VPP_1") (pintype "input"))
      (node (ref "IC23") (pin "28") (pinfunction "VCC_28") (pintype "power_in"))
      (node (ref "IC24") (pin "20") (pinfunction "VCC_20") (pintype "power_in"))
      (node (ref "IC24") (pin "22") (pinfunction "CS0_22") (pintype "input"))
      (node (ref "IC24") (pin "24") (pinfunction "CS1_24") (pintype "input"))
      (node (ref "IC27") (pin "10") (pinfunction "R_10") (pintype "input"))
      (node (ref "IC27") (pin "14") (pinfunction "V+_14") (pintype "power_in"))
      (node (ref "IC27") (pin "4") (pinfunction "R_4") (pintype "input"))
      (node (ref "JP4") (pin "2") (pinfunction "2_2") (pintype "passive"))
      (node (ref "QG1") (pin "14") (pinfunction "VCC_14") (pintype "power_in"))
      (node (ref "R1") (pin "2") (pinfunction "2_2") (pintype "passive"))
      (node (ref "R12") (pin "2") (pinfunction "2_2") (pintype "passive"))
      (node (ref "R14") (pin "2") (pinfunction "2_2") (pintype "passive"))
      (node (ref "R2") (pin "2") (pinfunction "2_2") (pintype "passive"))
      (node (ref "R3") (pin "2") (pinfunction "2_2") (pintype "passive"))
      (node (ref "R5") (pin "2") (pinfunction "2_2") (pintype "passive"))
      (node (ref "R6") (pin "2") (pinfunction "2_2") (pintype "passive"))
      (node (ref "R7") (pin "2") (pinfunction "2_2") (pintype "passive"))
      (node (ref "R8") (pin "2") (pinfunction "2_2") (pintype "passive"))
      (node (ref "R9") (pin "2") (pinfunction "2_2") (pintype "passive"))
    )
    (net (code "102") (name "unconnected-(COM-Pad1)") (class "Default")
      (node (ref "COM") (pin "1") (pinfunction "1_1") (pintype "passive"))
    )
    (net (code "103") (name "unconnected-(COM-Pad9)") (class "Default")
      (node (ref "COM") (pin "9") (pinfunction "9_9") (pintype "passive"))
    )
    (net (code "104") (name "unconnected-(IC17A-AVMA-Pad36)") (class "Default")
      (node (ref "IC17") (pin "36") (pinfunction "AVMA_36") (pintype "output"))
    )
    (net (code "105") (name "unconnected-(IC17A-BA-Pad6)") (class "Default")
      (node (ref "IC17") (pin "6") (pinfunction "BA_6") (pintype "output"))
    )
    (net (code "106") (name "unconnected-(IC17A-BS-Pad5)") (class "Default")
      (node (ref "IC17") (pin "5") (pinfunction "BS_5") (pintype "output"))
    )
    (net (code "107") (name "unconnected-(IC17A-BUSY-Pad33)") (class "Default")
      (node (ref "IC17") (pin "33") (pinfunction "BUSY_33") (pintype "output"))
    )
    (net (code "108") (name "unconnected-(IC17A-LIC-Pad38)") (class "Default")
      (node (ref "IC17") (pin "38") (pinfunction "LIC_38") (pintype "output"))
    )
    (net (code "109") (name "unconnected-(IC19A-Y0-Pad15)") (class "Default")
      (node (ref "IC19") (pin "15") (pinfunction "Y0_15") (pintype "output"))
    )
    (net (code "110") (name "unconnected-(IC19A-Y1-Pad14)") (class "Default")
      (node (ref "IC19") (pin "14") (pinfunction "Y1_14") (pintype "output"))
    )
    (net (code "111") (name "unconnected-(IC19A-Y2-Pad13)") (class "Default")
      (node (ref "IC19") (pin "13") (pinfunction "Y2_13") (pintype "output"))
    )
    (net (code "112") (name "unconnected-(IC19A-Y3-Pad12)") (class "Default")
      (node (ref "IC19") (pin "12") (pinfunction "Y3_12") (pintype "output"))
    )
    (net (code "113") (name "unconnected-(IC19A-Y4-Pad11)") (class "Default")
      (node (ref "IC19") (pin "11") (pinfunction "Y4_11") (pintype "output"))
    )
    (net (code "114") (name "unconnected-(IC19A-Y5-Pad10)") (class "Default")
      (node (ref "IC19") (pin "10") (pinfunction "Y5_10") (pintype "output"))
    )
    (net (code "115") (name "unconnected-(IC20A-R2OUT-Pad9)") (class "Default")
      (node (ref "IC20") (pin "9") (pinfunction "R2OUT_9") (pintype "output"))
    )
    (net (code "116") (name "unconnected-(IC22-NC-Pad1)") (class "Default")
      (node (ref "IC22") (pin "1") (pinfunction "NC_1") (pintype "no_connect"))
    )
    (net (code "117") (name "unconnected-(IC28A-Y1-Pad5)") (class "Default")
      (node (ref "IC28") (pin "5") (pinfunction "Y1_5") (pintype "output"))
    )
    (net (code "118") (name "unconnected-(IC28A-Y2-Pad6)") (class "Default")
      (node (ref "IC28") (pin "6") (pinfunction "Y2_6") (pintype "output"))
    )
    (net (code "119") (name "unconnected-(IC28B-Y0-Pad12)") (class "Default")
      (node (ref "IC28") (pin "12") (pinfunction "Y0_12") (pintype "output"))
    )
    (net (code "120") (name "~{4-B}") (class "Default")
      (node (ref "IC28") (pin "9") (pinfunction "Y3_9") (pintype "output"))
      (node (ref "IC29") (pin "20") (pinfunction "~{CE}_20") (pintype "input"))
      (node (ref "IC29") (pin "22") (pinfunction "~{OE}_22") (pintype "input"))
    )
    (net (code "121") (name "~{0123}") (class "Default")
      (node (ref "IC19") (pin "5") (pinfunction "G2B_5") (pintype "input"))
      (node (ref "IC22") (pin "20") (pinfunction "~{CS1}_20") (pintype "input"))
      (node (ref "IC22") (pin "22") (pinfunction "~{OE}_22") (pintype "input"))
      (node (ref "IC28") (pin "11") (pinfunction "Y1_11") (pintype "output"))
    )
    (net (code "122") (name "~{CDEF}") (class "Default")
      (node (ref "IC23") (pin "20") (pinfunction "~{CE}_20") (pintype "input"))
      (node (ref "IC23") (pin "22") (pinfunction "~{OE}_22") (pintype "input"))
      (node (ref "IC28") (pin "10") (pinfunction "Y2_10") (pintype "output"))
    )
    (net (code "123") (name "~{EP1}") (class "Default")
      (node (ref "IC28") (pin "14") (pinfunction "A_14") (pintype "input"))
      (node (ref "IC28") (pin "7") (pinfunction "Y3_7") (pintype "output"))
    )
    (net (code "124") (name "~{FIRQ}") (class "Default")
      (node (ref "IC17") (pin "4") (pinfunction "FIRQ_4") (pintype "input"))
      (node (ref "IC24") (pin "37") (pinfunction "IRQB_37") (pintype "open_collector"))
      (node (ref "IC24") (pin "38") (pinfunction "IRQA_38") (pintype "open_collector"))
      (node (ref "R8") (pin "1") (pinfunction "1_1") (pintype "passive"))
    )
    (net (code "125") (name "~{HLT}") (class "Default")
      (node (ref "IC17") (pin "40") (pinfunction "HALT_40") (pintype "input"))
      (node (ref "R5") (pin "1") (pinfunction "1_1") (pintype "passive"))
    )
    (net (code "126") (name "~{IO-E}") (class "Default")
      (node (ref "IC19") (pin "9") (pinfunction "Y6_9") (pintype "output"))
      (node (ref "IC24") (pin "23") (pinfunction "CS2_23") (pintype "input"))
    )
    (net (code "127") (name "~{IO-F}") (class "Default")
      (node (ref "IC19") (pin "7") (pinfunction "Y7_7") (pintype "output"))
      (node (ref "IC21") (pin "9") (pinfunction "CS2_9") (pintype "input"))
    )
    (net (code "128") (name "~{IRQ}") (class "Default")
      (node (ref "IC17") (pin "3") (pinfunction "IRQ_3") (pintype "input"))
      (node (ref "IC21") (pin "7") (pinfunction "IRQ_7") (pintype "output"))
      (node (ref "R7") (pin "1") (pinfunction "1_1") (pintype "passive"))
    )
    (net (code "129") (name "~{NMI}") (class "Default")
      (node (ref "IC17") (pin "2") (pinfunction "NMI_2") (pintype "input"))
      (node (ref "R6") (pin "1") (pinfunction "1_1") (pintype "passive"))
    )
    (net (code "130") (name "~{RST}") (class "Default")
      (node (ref "IC17") (pin "37") (pinfunction "RESET_37") (pintype "input"))
      (node (ref "IC18") (pin "6") (pinfunction "O_6") (pintype "output"))
      (node (ref "IC24") (pin "34") (pinfunction "RESET_34") (pintype "input"))
    )
  )
)
